# led_logger_v3.net
KiCad netlist of a schematic drawn in EAGLE
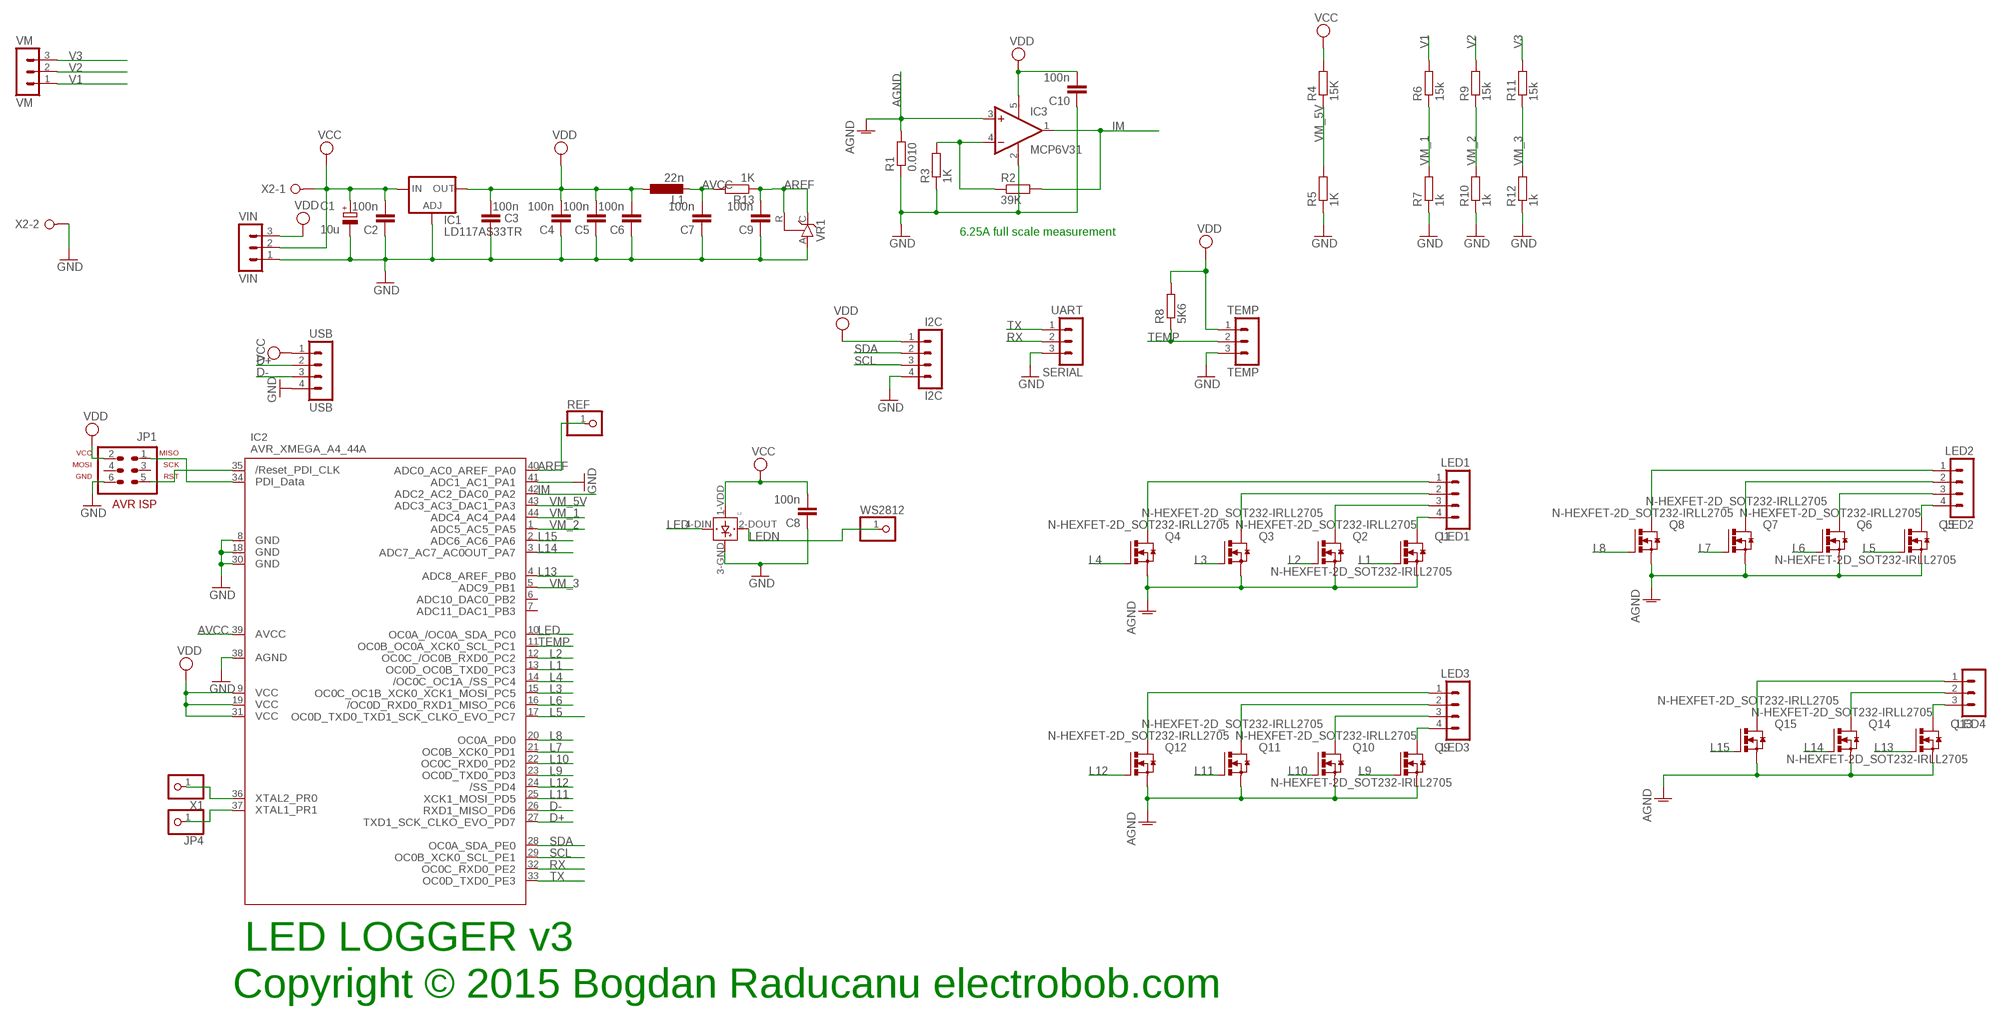
[diagram p0: schematic, sheet 1]

(export (version "E")
  (design (tool "Eeschema 10.0.6"))
  (components
    (comp (ref "C1")
      (value "10u")
      (footprint "eagle-import:SMC_A")
      (libsource (lib "eagle-import") (part "CPOL-EUSMCA"))
    )
    (comp (ref "C2")
      (value "100n")
      (footprint "eagle-import:C0805")
      (libsource (lib "eagle-import") (part "C-EUC0805"))
    )
    (comp (ref "C3")
      (value "100n")
      (footprint "eagle-import:C0805")
      (libsource (lib "eagle-import") (part "C-EUC0805"))
    )
    (comp (ref "C4")
      (value "100n")
      (footprint "eagle-import:C0805")
      (libsource (lib "eagle-import") (part "C-EUC0805"))
    )
    (comp (ref "C5")
      (value "100n")
      (footprint "eagle-import:C0805")
      (libsource (lib "eagle-import") (part "C-EUC0805"))
    )
    (comp (ref "C6")
      (value "100n")
      (footprint "eagle-import:C0805")
      (libsource (lib "eagle-import") (part "C-EUC0805"))
    )
    (comp (ref "C7")
      (value "100n")
      (footprint "eagle-import:C0805")
      (libsource (lib "eagle-import") (part "C-EUC0805"))
    )
    (comp (ref "C8")
      (value "100n")
      (footprint "eagle-import:C0805")
      (libsource (lib "eagle-import") (part "C-EUC0805"))
    )
    (comp (ref "C9")
      (value "100n")
      (footprint "eagle-import:C1206")
      (libsource (lib "eagle-import") (part "C-EUC1206"))
    )
    (comp (ref "C10")
      (value "100n")
      (footprint "eagle-import:C0805")
      (libsource (lib "eagle-import") (part "C-EUC0805"))
    )
    (comp (ref "I2C")
      (value "I2C")
      (footprint "eagle-import:MA04-1")
      (libsource (lib "eagle-import") (part "MA04-1"))
    )
    (comp (ref "IC1")
      (value "LD117AS33TR")
      (footprint "eagle-import:SOT223")
      (libsource (lib "eagle-import") (part "LD117A?S33TR"))
    )
    (comp (ref "IC2")
      (value "AVR_XMEGA_A4_44A")
      (footprint "eagle-import:TQFP44")
      (libsource (lib "eagle-import") (part "AVR_XMEGA_A4_44A"))
    )
    (comp (ref "IC3")
      (value "MCP6V31")
      (footprint "eagle-import:SOT23-5")
      (libsource (lib "eagle-import") (part "MCP601OT"))
    )
    (comp (ref "JP1")
      (value "AVR-ISP-6VERT")
      (footprint "eagle-import:AVR-ISP-6")
      (libsource (lib "eagle-import") (part "AVR-ISP-6VERT"))
    )
    (comp (ref "JP4")
      (value "PINHD-1X1")
      (footprint "eagle-import:1X01")
      (libsource (lib "eagle-import") (part "PINHD-1X1"))
    )
    (comp (ref "L1")
      (value "22n")
      (footprint "eagle-import:L2012C")
      (libsource (lib "eagle-import") (part "L-EUL2012C"))
    )
    (comp (ref "L2")
      (value "WS2812B")
      (footprint "eagle-import:WS2812B")
      (libsource (lib "eagle-import") (part "WS2812B"))
    )
    (comp (ref "LED1")
      (value "LED1")
      (footprint "eagle-import:MA04-1")
      (libsource (lib "eagle-import") (part "MA04-1"))
    )
    (comp (ref "LED2")
      (value "LED2")
      (footprint "eagle-import:MA04-1")
      (libsource (lib "eagle-import") (part "MA04-1"))
    )
    (comp (ref "LED3")
      (value "LED3")
      (footprint "eagle-import:MA04-1")
      (libsource (lib "eagle-import") (part "MA04-1"))
    )
    (comp (ref "LED4")
      (value "MA03-1")
      (footprint "eagle-import:MA03-1")
      (libsource (lib "eagle-import") (part "MA03-1"))
    )
    (comp (ref "Q1")
      (value "N-HEXFET-2D_SOT232-IRLL2705")
      (footprint "eagle-import:SOT223")
      (libsource (lib "eagle-import") (part "N-HEXFET-2D_?-SOT232IRLL2705"))
    )
    (comp (ref "Q2")
      (value "N-HEXFET-2D_SOT232-IRLL2705")
      (footprint "eagle-import:SOT223")
      (libsource (lib "eagle-import") (part "N-HEXFET-2D_?-SOT232IRLL2705"))
    )
    (comp (ref "Q3")
      (value "N-HEXFET-2D_SOT232-IRLL2705")
      (footprint "eagle-import:SOT223")
      (libsource (lib "eagle-import") (part "N-HEXFET-2D_?-SOT232IRLL2705"))
    )
    (comp (ref "Q4")
      (value "N-HEXFET-2D_SOT232-IRLL2705")
      (footprint "eagle-import:SOT223")
      (libsource (lib "eagle-import") (part "N-HEXFET-2D_?-SOT232IRLL2705"))
    )
    (comp (ref "Q5")
      (value "N-HEXFET-2D_SOT232-IRLL2705")
      (footprint "eagle-import:SOT223")
      (libsource (lib "eagle-import") (part "N-HEXFET-2D_?-SOT232IRLL2705"))
    )
    (comp (ref "Q6")
      (value "N-HEXFET-2D_SOT232-IRLL2705")
      (footprint "eagle-import:SOT223")
      (libsource (lib "eagle-import") (part "N-HEXFET-2D_?-SOT232IRLL2705"))
    )
    (comp (ref "Q7")
      (value "N-HEXFET-2D_SOT232-IRLL2705")
      (footprint "eagle-import:SOT223")
      (libsource (lib "eagle-import") (part "N-HEXFET-2D_?-SOT232IRLL2705"))
    )
    (comp (ref "Q8")
      (value "N-HEXFET-2D_SOT232-IRLL2705")
      (footprint "eagle-import:SOT223")
      (libsource (lib "eagle-import") (part "N-HEXFET-2D_?-SOT232IRLL2705"))
    )
    (comp (ref "Q9")
      (value "N-HEXFET-2D_SOT232-IRLL2705")
      (footprint "eagle-import:SOT223")
      (libsource (lib "eagle-import") (part "N-HEXFET-2D_?-SOT232IRLL2705"))
    )
    (comp (ref "Q10")
      (value "N-HEXFET-2D_SOT232-IRLL2705")
      (footprint "eagle-import:SOT223")
      (libsource (lib "eagle-import") (part "N-HEXFET-2D_?-SOT232IRLL2705"))
    )
    (comp (ref "Q11")
      (value "N-HEXFET-2D_SOT232-IRLL2705")
      (footprint "eagle-import:SOT223")
      (libsource (lib "eagle-import") (part "N-HEXFET-2D_?-SOT232IRLL2705"))
    )
    (comp (ref "Q12")
      (value "N-HEXFET-2D_SOT232-IRLL2705")
      (footprint "eagle-import:SOT223")
      (libsource (lib "eagle-import") (part "N-HEXFET-2D_?-SOT232IRLL2705"))
    )
    (comp (ref "Q13")
      (value "N-HEXFET-2D_SOT232-IRLL2705")
      (footprint "eagle-import:SOT223")
      (libsource (lib "eagle-import") (part "N-HEXFET-2D_?-SOT232IRLL2705"))
    )
    (comp (ref "Q14")
      (value "N-HEXFET-2D_SOT232-IRLL2705")
      (footprint "eagle-import:SOT223")
      (libsource (lib "eagle-import") (part "N-HEXFET-2D_?-SOT232IRLL2705"))
    )
    (comp (ref "Q15")
      (value "N-HEXFET-2D_SOT232-IRLL2705")
      (footprint "eagle-import:SOT223")
      (libsource (lib "eagle-import") (part "N-HEXFET-2D_?-SOT232IRLL2705"))
    )
    (comp (ref "R1")
      (value "0.010")
      (footprint "eagle-import:0414V")
      (libsource (lib "eagle-import") (part "R-EU_0414/5V"))
    )
    (comp (ref "R2")
      (value "39K")
      (footprint "eagle-import:R0805")
      (libsource (lib "eagle-import") (part "R-EU_R0805"))
    )
    (comp (ref "R3")
      (value "1K")
      (footprint "eagle-import:R0805")
      (libsource (lib "eagle-import") (part "R-EU_R0805"))
    )
    (comp (ref "R4")
      (value "15K")
      (footprint "eagle-import:R0805")
      (libsource (lib "eagle-import") (part "R-EU_R0805"))
    )
    (comp (ref "R5")
      (value "1K")
      (footprint "eagle-import:R0805")
      (libsource (lib "eagle-import") (part "R-EU_R0805"))
    )
    (comp (ref "R6")
      (value "15k")
      (footprint "eagle-import:R0805")
      (libsource (lib "eagle-import") (part "R-EU_R0805"))
    )
    (comp (ref "R7")
      (value "1k")
      (footprint "eagle-import:R0805")
      (libsource (lib "eagle-import") (part "R-EU_R0805"))
    )
    (comp (ref "R8")
      (value "5K6")
      (footprint "eagle-import:R0805")
      (libsource (lib "eagle-import") (part "R-EU_R0805"))
    )
    (comp (ref "R9")
      (value "15k")
      (footprint "eagle-import:R0805")
      (libsource (lib "eagle-import") (part "R-EU_R0805"))
    )
    (comp (ref "R10")
      (value "1k")
      (footprint "eagle-import:R0805")
      (libsource (lib "eagle-import") (part "R-EU_R0805"))
    )
    (comp (ref "R11")
      (value "15k")
      (footprint "eagle-import:R0805")
      (libsource (lib "eagle-import") (part "R-EU_R0805"))
    )
    (comp (ref "R12")
      (value "1k")
      (footprint "eagle-import:R0805")
      (libsource (lib "eagle-import") (part "R-EU_R0805"))
    )
    (comp (ref "R13")
      (value "1K")
      (footprint "eagle-import:R0805")
      (libsource (lib "eagle-import") (part "R-EU_R0805"))
    )
    (comp (ref "REF")
      (value "PINHD-1X1")
      (footprint "eagle-import:1X01")
      (libsource (lib "eagle-import") (part "PINHD-1X1"))
    )
    (comp (ref "SERIAL")
      (value "UART")
      (footprint "eagle-import:MA03-1")
      (libsource (lib "eagle-import") (part "MA03-1"))
    )
    (comp (ref "TEMP")
      (value "TEMP")
      (footprint "eagle-import:MA03-1")
      (libsource (lib "eagle-import") (part "MA03-1"))
    )
    (comp (ref "USB")
      (value "USB")
      (footprint "eagle-import:MA04-1")
      (libsource (lib "eagle-import") (part "MA04-1"))
    )
    (comp (ref "VIN")
      (value "VIN")
      (footprint "eagle-import:MA03-1")
      (libsource (lib "eagle-import") (part "MA03-1"))
    )
    (comp (ref "VM")
      (value "VM")
      (footprint "eagle-import:MA03-1")
      (libsource (lib "eagle-import") (part "MA03-1"))
    )
    (comp (ref "VR1")
      (value "TL431CLP")
      (footprint "eagle-import:TO92-CLP")
      (libsource (lib "eagle-import") (part "TL431CLP"))
    )
    (comp (ref "WS2812")
      (value "PINHD-1X1")
      (footprint "eagle-import:1X01")
      (libsource (lib "eagle-import") (part "PINHD-1X1"))
    )
    (comp (ref "X1")
      (value "PINHD-1X1")
      (footprint "eagle-import:1X01")
      (libsource (lib "eagle-import") (part "PINHD-1X1"))
    )
    (comp (ref "X2")
      (value "W237-02P")
      (footprint "eagle-import:W237-132")
      (libsource (lib "eagle-import") (part "W237-02P"))
    )
  )
  (nets
    (net (code "1") (name "/AREF") (class "Default")
      (node (ref "C9") (pin "2") (pinfunction "2_2") (pintype "passive"))
      (node (ref "IC2") (pin "40") (pinfunction "PA0_40") (pintype "bidirectional"))
      (node (ref "R13") (pin "1") (pinfunction "1_1") (pintype "passive"))
      (node (ref "REF") (pin "1") (pinfunction "1_1") (pintype "passive"))
      (node (ref "VR1") (pin "C") (pinfunction "C_C") (pintype "passive"))
      (node (ref "VR1") (pin "R") (pinfunction "R_R") (pintype "passive"))
    )
    (net (code "2") (name "/AVCC") (class "Default")
      (node (ref "C7") (pin "2") (pinfunction "2_2") (pintype "passive"))
      (node (ref "IC2") (pin "39") (pinfunction "AVCC_39") (pintype "bidirectional"))
      (node (ref "L1") (pin "2") (pinfunction "2_2") (pintype "passive"))
      (node (ref "R13") (pin "2") (pinfunction "2_2") (pintype "passive"))
    )
    (net (code "3") (name "/D+") (class "Default")
      (node (ref "IC2") (pin "27") (pinfunction "PD7_27") (pintype "bidirectional"))
      (node (ref "USB") (pin "2") (pinfunction "2_2") (pintype "passive"))
    )
    (net (code "4") (name "/D-") (class "Default")
      (node (ref "IC2") (pin "26") (pinfunction "PD6_26") (pintype "bidirectional"))
      (node (ref "USB") (pin "3") (pinfunction "3_3") (pintype "passive"))
    )
    (net (code "5") (name "/IM") (class "Default")
      (node (ref "IC2") (pin "42") (pinfunction "PA2_42") (pintype "bidirectional"))
      (node (ref "IC3") (pin "1") (pinfunction "OUT_1") (pintype "output"))
      (node (ref "R2") (pin "2") (pinfunction "2_2") (pintype "passive"))
    )
    (net (code "6") (name "/L1") (class "Default")
      (node (ref "IC2") (pin "13") (pinfunction "PC3_13") (pintype "bidirectional"))
      (node (ref "Q1") (pin "1") (pinfunction "G_1") (pintype "passive"))
    )
    (net (code "7") (name "/L2") (class "Default")
      (node (ref "IC2") (pin "12") (pinfunction "PC2_12") (pintype "bidirectional"))
      (node (ref "Q2") (pin "1") (pinfunction "G_1") (pintype "passive"))
    )
    (net (code "8") (name "/L3") (class "Default")
      (node (ref "IC2") (pin "15") (pinfunction "PC5_15") (pintype "bidirectional"))
      (node (ref "Q3") (pin "1") (pinfunction "G_1") (pintype "passive"))
    )
    (net (code "9") (name "/L4") (class "Default")
      (node (ref "IC2") (pin "14") (pinfunction "PC4_14") (pintype "bidirectional"))
      (node (ref "Q4") (pin "1") (pinfunction "G_1") (pintype "passive"))
    )
    (net (code "10") (name "/L5") (class "Default")
      (node (ref "IC2") (pin "17") (pinfunction "PC7_17") (pintype "bidirectional"))
      (node (ref "Q5") (pin "1") (pinfunction "G_1") (pintype "passive"))
    )
    (net (code "11") (name "/L6") (class "Default")
      (node (ref "IC2") (pin "16") (pinfunction "PC6_16") (pintype "bidirectional"))
      (node (ref "Q6") (pin "1") (pinfunction "G_1") (pintype "passive"))
    )
    (net (code "12") (name "/L7") (class "Default")
      (node (ref "IC2") (pin "21") (pinfunction "PD1_21") (pintype "bidirectional"))
      (node (ref "Q7") (pin "1") (pinfunction "G_1") (pintype "passive"))
    )
    (net (code "13") (name "/L8") (class "Default")
      (node (ref "IC2") (pin "20") (pinfunction "PD0_20") (pintype "bidirectional"))
      (node (ref "Q8") (pin "1") (pinfunction "G_1") (pintype "passive"))
    )
    (net (code "14") (name "/L9") (class "Default")
      (node (ref "IC2") (pin "23") (pinfunction "PD3_23") (pintype "bidirectional"))
      (node (ref "Q9") (pin "1") (pinfunction "G_1") (pintype "passive"))
    )
    (net (code "15") (name "/L10") (class "Default")
      (node (ref "IC2") (pin "22") (pinfunction "PD2_22") (pintype "bidirectional"))
      (node (ref "Q10") (pin "1") (pinfunction "G_1") (pintype "passive"))
    )
    (net (code "16") (name "/L11") (class "Default")
      (node (ref "IC2") (pin "25") (pinfunction "PD5_25") (pintype "bidirectional"))
      (node (ref "Q11") (pin "1") (pinfunction "G_1") (pintype "passive"))
    )
    (net (code "17") (name "/L12") (class "Default")
      (node (ref "IC2") (pin "24") (pinfunction "PD4_24") (pintype "bidirectional"))
      (node (ref "Q12") (pin "1") (pinfunction "G_1") (pintype "passive"))
    )
    (net (code "18") (name "/L13") (class "Default")
      (node (ref "IC2") (pin "4") (pinfunction "PB0_4") (pintype "bidirectional"))
      (node (ref "Q13") (pin "1") (pinfunction "G_1") (pintype "passive"))
    )
    (net (code "19") (name "/L14") (class "Default")
      (node (ref "IC2") (pin "3") (pinfunction "PA7_3") (pintype "bidirectional"))
      (node (ref "Q14") (pin "1") (pinfunction "G_1") (pintype "passive"))
    )
    (net (code "20") (name "/L15") (class "Default")
      (node (ref "IC2") (pin "2") (pinfunction "PA6_2") (pintype "bidirectional"))
      (node (ref "Q15") (pin "1") (pinfunction "G_1") (pintype "passive"))
    )
    (net (code "21") (name "/LED") (class "Default")
      (node (ref "IC2") (pin "10") (pinfunction "PC0_10") (pintype "bidirectional"))
      (node (ref "L2") (pin "4-DIN") (pinfunction "DIN_4-DIN") (pintype "input"))
    )
    (net (code "22") (name "/LEDN") (class "Default")
      (node (ref "L2") (pin "2-DOUT") (pinfunction "DOUT_2-DOUT") (pintype "output"))
      (node (ref "WS2812") (pin "1") (pinfunction "1_1") (pintype "passive"))
    )
    (net (code "23") (name "/RX") (class "Default")
      (node (ref "IC2") (pin "32") (pinfunction "PE2_32") (pintype "bidirectional"))
      (node (ref "SERIAL") (pin "2") (pinfunction "2_2") (pintype "passive"))
    )
    (net (code "24") (name "/SCL") (class "Default")
      (node (ref "I2C") (pin "3") (pinfunction "3_3") (pintype "passive"))
      (node (ref "IC2") (pin "29") (pinfunction "PE1_29") (pintype "bidirectional"))
    )
    (net (code "25") (name "/SDA") (class "Default")
      (node (ref "I2C") (pin "2") (pinfunction "2_2") (pintype "passive"))
      (node (ref "IC2") (pin "28") (pinfunction "PE0_28") (pintype "bidirectional"))
    )
    (net (code "26") (name "/TEMP") (class "Default")
      (node (ref "IC2") (pin "11") (pinfunction "PC1_11") (pintype "bidirectional"))
      (node (ref "R8") (pin "1") (pinfunction "1_1") (pintype "passive"))
      (node (ref "TEMP") (pin "2") (pinfunction "2_2") (pintype "passive"))
    )
    (net (code "27") (name "/TX") (class "Default")
      (node (ref "IC2") (pin "33") (pinfunction "PE3_33") (pintype "bidirectional"))
      (node (ref "SERIAL") (pin "1") (pinfunction "1_1") (pintype "passive"))
    )
    (net (code "28") (name "/V1") (class "Default")
      (node (ref "R6") (pin "2") (pinfunction "2_2") (pintype "passive"))
      (node (ref "VM") (pin "1") (pinfunction "1_1") (pintype "passive"))
    )
    (net (code "29") (name "/V2") (class "Default")
      (node (ref "R9") (pin "2") (pinfunction "2_2") (pintype "passive"))
      (node (ref "VM") (pin "2") (pinfunction "2_2") (pintype "passive"))
    )
    (net (code "30") (name "/V3") (class "Default")
      (node (ref "R11") (pin "2") (pinfunction "2_2") (pintype "passive"))
      (node (ref "VM") (pin "3") (pinfunction "3_3") (pintype "passive"))
    )
    (net (code "31") (name "/VM_1") (class "Default")
      (node (ref "IC2") (pin "44") (pinfunction "PA4_44") (pintype "bidirectional"))
      (node (ref "R6") (pin "1") (pinfunction "1_1") (pintype "passive"))
      (node (ref "R7") (pin "2") (pinfunction "2_2") (pintype "passive"))
    )
    (net (code "32") (name "/VM_2") (class "Default")
      (node (ref "IC2") (pin "1") (pinfunction "PA5_1") (pintype "bidirectional"))
      (node (ref "R10") (pin "2") (pinfunction "2_2") (pintype "passive"))
      (node (ref "R9") (pin "1") (pinfunction "1_1") (pintype "passive"))
    )
    (net (code "33") (name "/VM_3") (class "Default")
      (node (ref "IC2") (pin "5") (pinfunction "PB1_5") (pintype "bidirectional"))
      (node (ref "R11") (pin "1") (pinfunction "1_1") (pintype "passive"))
      (node (ref "R12") (pin "2") (pinfunction "2_2") (pintype "passive"))
    )
    (net (code "34") (name "/VM_5V") (class "Default")
      (node (ref "IC2") (pin "43") (pinfunction "PA3_43") (pintype "bidirectional"))
      (node (ref "R4") (pin "1") (pinfunction "1_1") (pintype "passive"))
      (node (ref "R5") (pin "2") (pinfunction "2_2") (pintype "passive"))
    )
    (net (code "35") (name "AGND") (class "Default")
      (node (ref "IC3") (pin "3") (pinfunction "+IN_3") (pintype "input"))
      (node (ref "Q1") (pin "3") (pinfunction "S_3") (pintype "passive"))
      (node (ref "Q10") (pin "3") (pinfunction "S_3") (pintype "passive"))
      (node (ref "Q11") (pin "3") (pinfunction "S_3") (pintype "passive"))
      (node (ref "Q12") (pin "3") (pinfunction "S_3") (pintype "passive"))
      (node (ref "Q13") (pin "3") (pinfunction "S_3") (pintype "passive"))
      (node (ref "Q14") (pin "3") (pinfunction "S_3") (pintype "passive"))
      (node (ref "Q15") (pin "3") (pinfunction "S_3") (pintype "passive"))
      (node (ref "Q2") (pin "3") (pinfunction "S_3") (pintype "passive"))
      (node (ref "Q3") (pin "3") (pinfunction "S_3") (pintype "passive"))
      (node (ref "Q4") (pin "3") (pinfunction "S_3") (pintype "passive"))
      (node (ref "Q5") (pin "3") (pinfunction "S_3") (pintype "passive"))
      (node (ref "Q6") (pin "3") (pinfunction "S_3") (pintype "passive"))
      (node (ref "Q7") (pin "3") (pinfunction "S_3") (pintype "passive"))
      (node (ref "Q8") (pin "3") (pinfunction "S_3") (pintype "passive"))
      (node (ref "Q9") (pin "3") (pinfunction "S_3") (pintype "passive"))
      (node (ref "R1") (pin "2") (pinfunction "2_2") (pintype "passive"))
    )
    (net (code "36") (name "GND") (class "Default")
      (node (ref "C1") (pin "-") (pinfunction "-_-") (pintype "passive"))
      (node (ref "C10") (pin "1") (pinfunction "1_1") (pintype "passive"))
      (node (ref "C2") (pin "1") (pinfunction "1_1") (pintype "passive"))
      (node (ref "C3") (pin "1") (pinfunction "1_1") (pintype "passive"))
      (node (ref "C4") (pin "1") (pinfunction "1_1") (pintype "passive"))
      (node (ref "C5") (pin "1") (pinfunction "1_1") (pintype "passive"))
      (node (ref "C6") (pin "1") (pinfunction "1_1") (pintype "passive"))
      (node (ref "C7") (pin "1") (pinfunction "1_1") (pintype "passive"))
      (node (ref "C8") (pin "1") (pinfunction "1_1") (pintype "passive"))
      (node (ref "C9") (pin "1") (pinfunction "1_1") (pintype "passive"))
      (node (ref "I2C") (pin "4") (pinfunction "4_4") (pintype "passive"))
      (node (ref "IC1") (pin "1") (pinfunction "ADJ_1") (pintype "input"))
      (node (ref "IC2") (pin "18") (pinfunction "GND2_18") (pintype "bidirectional"))
      (node (ref "IC2") (pin "30") (pinfunction "GND3_30") (pintype "bidirectional"))
      (node (ref "IC2") (pin "38") (pinfunction "AGND_38") (pintype "bidirectional"))
      (node (ref "IC2") (pin "41") (pinfunction "PA1_41") (pintype "bidirectional"))
      (node (ref "IC2") (pin "8") (pinfunction "GND1_8") (pintype "bidirectional"))
      (node (ref "IC3") (pin "2") (pinfunction "V-_2") (pintype "power_in"))
      (node (ref "JP1") (pin "6") (pinfunction "6_6") (pintype "passive"))
      (node (ref "L2") (pin "3-GND") (pinfunction "GND_3-GND") (pintype "bidirectional"))
      (node (ref "R1") (pin "1") (pinfunction "1_1") (pintype "passive"))
      (node (ref "R10") (pin "1") (pinfunction "1_1") (pintype "passive"))
      (node (ref "R12") (pin "1") (pinfunction "1_1") (pintype "passive"))
      (node (ref "R3") (pin "1") (pinfunction "1_1") (pintype "passive"))
      (node (ref "R5") (pin "1") (pinfunction "1_1") (pintype "passive"))
      (node (ref "R7") (pin "1") (pinfunction "1_1") (pintype "passive"))
      (node (ref "SERIAL") (pin "3") (pinfunction "3_3") (pintype "passive"))
      (node (ref "TEMP") (pin "3") (pinfunction "3_3") (pintype "passive"))
      (node (ref "USB") (pin "4") (pinfunction "4_4") (pintype "passive"))
      (node (ref "VIN") (pin "1") (pinfunction "1_1") (pintype "passive"))
      (node (ref "VR1") (pin "A") (pinfunction "A_A") (pintype "passive"))
      (node (ref "X2") (pin "2") (pinfunction "KL_2") (pintype "passive"))
    )
    (net (code "37") (name "Net-(IC2-PDI_DATA)") (class "Default")
      (node (ref "IC2") (pin "34") (pinfunction "PDI_DATA_34") (pintype "bidirectional"))
      (node (ref "JP1") (pin "1") (pinfunction "1_1") (pintype "passive"))
    )
    (net (code "38") (name "Net-(IC2-PR0)") (class "Default")
      (node (ref "IC2") (pin "36") (pinfunction "PR0_36") (pintype "bidirectional"))
      (node (ref "X1") (pin "1") (pinfunction "1_1") (pintype "passive"))
    )
    (net (code "39") (name "Net-(IC2-PR1)") (class "Default")
      (node (ref "IC2") (pin "37") (pinfunction "PR1_37") (pintype "bidirectional"))
      (node (ref "JP4") (pin "1") (pinfunction "1_1") (pintype "passive"))
    )
    (net (code "40") (name "Net-(IC2-RESET)") (class "Default")
      (node (ref "IC2") (pin "35") (pinfunction "RESET_35") (pintype "bidirectional"))
      (node (ref "JP1") (pin "5") (pinfunction "5_5") (pintype "passive"))
    )
    (net (code "41") (name "Net-(IC3--IN)") (class "Default")
      (node (ref "IC3") (pin "4") (pinfunction "-IN_4") (pintype "input"))
      (node (ref "R2") (pin "1") (pinfunction "1_1") (pintype "passive"))
      (node (ref "R3") (pin "2") (pinfunction "2_2") (pintype "passive"))
    )
    (net (code "42") (name "Net-(LED1-Pad1)") (class "Default")
      (node (ref "LED1") (pin "1") (pinfunction "1_1") (pintype "passive"))
      (node (ref "Q4") (pin "2") (pinfunction "D_2") (pintype "passive"))
      (node (ref "Q4") (pin "4") (pinfunction "D_4") (pintype "passive"))
    )
    (net (code "43") (name "Net-(LED1-Pad2)") (class "Default")
      (node (ref "LED1") (pin "2") (pinfunction "2_2") (pintype "passive"))
      (node (ref "Q3") (pin "2") (pinfunction "D_2") (pintype "passive"))
      (node (ref "Q3") (pin "4") (pinfunction "D_4") (pintype "passive"))
    )
    (net (code "44") (name "Net-(LED1-Pad3)") (class "Default")
      (node (ref "LED1") (pin "3") (pinfunction "3_3") (pintype "passive"))
      (node (ref "Q2") (pin "2") (pinfunction "D_2") (pintype "passive"))
      (node (ref "Q2") (pin "4") (pinfunction "D_4") (pintype "passive"))
    )
    (net (code "45") (name "Net-(LED1-Pad4)") (class "Default")
      (node (ref "LED1") (pin "4") (pinfunction "4_4") (pintype "passive"))
      (node (ref "Q1") (pin "2") (pinfunction "D_2") (pintype "passive"))
      (node (ref "Q1") (pin "4") (pinfunction "D_4") (pintype "passive"))
    )
    (net (code "46") (name "Net-(LED2-Pad1)") (class "Default")
      (node (ref "LED2") (pin "1") (pinfunction "1_1") (pintype "passive"))
      (node (ref "Q8") (pin "2") (pinfunction "D_2") (pintype "passive"))
      (node (ref "Q8") (pin "4") (pinfunction "D_4") (pintype "passive"))
    )
    (net (code "47") (name "Net-(LED2-Pad2)") (class "Default")
      (node (ref "LED2") (pin "2") (pinfunction "2_2") (pintype "passive"))
      (node (ref "Q7") (pin "2") (pinfunction "D_2") (pintype "passive"))
      (node (ref "Q7") (pin "4") (pinfunction "D_4") (pintype "passive"))
    )
    (net (code "48") (name "Net-(LED2-Pad3)") (class "Default")
      (node (ref "LED2") (pin "3") (pinfunction "3_3") (pintype "passive"))
      (node (ref "Q6") (pin "2") (pinfunction "D_2") (pintype "passive"))
      (node (ref "Q6") (pin "4") (pinfunction "D_4") (pintype "passive"))
    )
    (net (code "49") (name "Net-(LED2-Pad4)") (class "Default")
      (node (ref "LED2") (pin "4") (pinfunction "4_4") (pintype "passive"))
      (node (ref "Q5") (pin "2") (pinfunction "D_2") (pintype "passive"))
      (node (ref "Q5") (pin "4") (pinfunction "D_4") (pintype "passive"))
    )
    (net (code "50") (name "Net-(LED3-Pad1)") (class "Default")
      (node (ref "LED3") (pin "1") (pinfunction "1_1") (pintype "passive"))
      (node (ref "Q12") (pin "2") (pinfunction "D_2") (pintype "passive"))
      (node (ref "Q12") (pin "4") (pinfunction "D_4") (pintype "passive"))
    )
    (net (code "51") (name "Net-(LED3-Pad2)") (class "Default")
      (node (ref "LED3") (pin "2") (pinfunction "2_2") (pintype "passive"))
      (node (ref "Q11") (pin "2") (pinfunction "D_2") (pintype "passive"))
      (node (ref "Q11") (pin "4") (pinfunction "D_4") (pintype "passive"))
    )
    (net (code "52") (name "Net-(LED3-Pad3)") (class "Default")
      (node (ref "LED3") (pin "3") (pinfunction "3_3") (pintype "passive"))
      (node (ref "Q10") (pin "2") (pinfunction "D_2") (pintype "passive"))
      (node (ref "Q10") (pin "4") (pinfunction "D_4") (pintype "passive"))
    )
    (net (code "53") (name "Net-(LED3-Pad4)") (class "Default")
      (node (ref "LED3") (pin "4") (pinfunction "4_4") (pintype "passive"))
      (node (ref "Q9") (pin "2") (pinfunction "D_2") (pintype "passive"))
      (node (ref "Q9") (pin "4") (pinfunction "D_4") (pintype "passive"))
    )
    (net (code "54") (name "Net-(LED4-Pad1)") (class "Default")
      (node (ref "LED4") (pin "1") (pinfunction "1_1") (pintype "passive"))
      (node (ref "Q15") (pin "2") (pinfunction "D_2") (pintype "passive"))
      (node (ref "Q15") (pin "4") (pinfunction "D_4") (pintype "passive"))
    )
    (net (code "55") (name "Net-(LED4-Pad2)") (class "Default")
      (node (ref "LED4") (pin "2") (pinfunction "2_2") (pintype "passive"))
      (node (ref "Q14") (pin "2") (pinfunction "D_2") (pintype "passive"))
      (node (ref "Q14") (pin "4") (pinfunction "D_4") (pintype "passive"))
    )
    (net (code "56") (name "Net-(LED4-Pad3)") (class "Default")
      (node (ref "LED4") (pin "3") (pinfunction "3_3") (pintype "passive"))
      (node (ref "Q13") (pin "2") (pinfunction "D_2") (pintype "passive"))
      (node (ref "Q13") (pin "4") (pinfunction "D_4") (pintype "passive"))
    )
    (net (code "57") (name "VCC") (class "Default")
      (node (ref "C1") (pin "+") (pinfunction "+_+") (pintype "passive"))
      (node (ref "C2") (pin "2") (pinfunction "2_2") (pintype "passive"))
      (node (ref "C8") (pin "2") (pinfunction "2_2") (pintype "passive"))
      (node (ref "IC1") (pin "3") (pinfunction "IN_3") (pintype "input"))
      (node (ref "L2") (pin "1-VDD") (pinfunction "VDD_1-VDD") (pintype "bidirectional"))
      (node (ref "R4") (pin "2") (pinfunction "2_2") (pintype "passive"))
      (node (ref "USB") (pin "1") (pinfunction "1_1") (pintype "passive"))
      (node (ref "VIN") (pin "2") (pinfunction "2_2") (pintype "passive"))
      (node (ref "X2") (pin "1") (pinfunction "KL_1") (pintype "passive"))
    )
    (net (code "58") (name "VDD") (class "Default")
      (node (ref "C10") (pin "2") (pinfunction "2_2") (pintype "passive"))
      (node (ref "C3") (pin "2") (pinfunction "2_2") (pintype "passive"))
      (node (ref "C4") (pin "2") (pinfunction "2_2") (pintype "passive"))
      (node (ref "C5") (pin "2") (pinfunction "2_2") (pintype "passive"))
      (node (ref "C6") (pin "2") (pinfunction "2_2") (pintype "passive"))
      (node (ref "I2C") (pin "1") (pinfunction "1_1") (pintype "passive"))
      (node (ref "IC1") (pin "4") (pinfunction "OUT_4") (pintype "passive"))
      (node (ref "IC2") (pin "19") (pinfunction "VCC2_19") (pintype "bidirectional"))
      (node (ref "IC2") (pin "31") (pinfunction "VCC3_31") (pintype "bidirectional"))
      (node (ref "IC2") (pin "9") (pinfunction "VCC1_9") (pintype "bidirectional"))
      (node (ref "IC3") (pin "5") (pinfunction "V+_5") (pintype "power_in"))
      (node (ref "JP1") (pin "2") (pinfunction "2_2") (pintype "passive"))
      (node (ref "L1") (pin "1") (pinfunction "1_1") (pintype "passive"))
      (node (ref "R8") (pin "2") (pinfunction "2_2") (pintype "passive"))
      (node (ref "TEMP") (pin "1") (pinfunction "1_1") (pintype "passive"))
      (node (ref "VIN") (pin "3") (pinfunction "3_3") (pintype "passive"))
    )
    (net (code "59") (name "unconnected-(IC2-PB2-Pad6)") (class "Default")
      (node (ref "IC2") (pin "6") (pinfunction "PB2_6") (pintype "bidirectional"))
    )
    (net (code "60") (name "unconnected-(IC2-PB3-Pad7)") (class "Default")
      (node (ref "IC2") (pin "7") (pinfunction "PB3_7") (pintype "bidirectional"))
    )
    (net (code "61") (name "unconnected-(JP1-Pad3)") (class "Default")
      (node (ref "JP1") (pin "3") (pinfunction "3_3") (pintype "passive"))
    )
    (net (code "62") (name "unconnected-(JP1-Pad4)") (class "Default")
      (node (ref "JP1") (pin "4") (pinfunction "4_4") (pintype "passive"))
    )
  )
)
